# ISO_I2C_ISO1540DR.net
KiCad netlist of a schematic drawn in Altium Designer
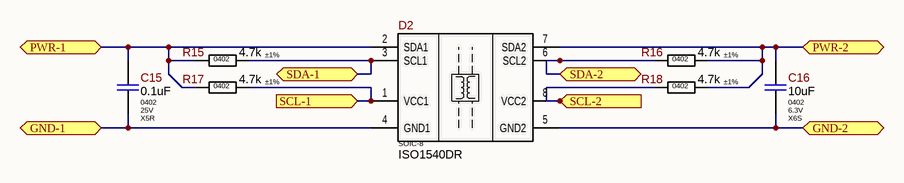
[diagram p0: ISO_I2C_ISO1540DR.SchDoc]

(export (version "E")
  (design (tool "Eeschema 10.0.6"))
  (components
    (comp (ref "C15")
      (value "0.1uF")
      (footprint "C_CERAMIC_0402_MED")
      (description "100nF 25V X5R ±10% 0402 Ceramic Capacitor RoHS")
      (fields
        (field (name "PACKAGE") "0402")
        (field (name "VOLTAGE") "25V")
        (field (name "DIELECTRIC TYPE") "X5R")
        (field (name "PART NUMBER") "CL05A104KA5NNNC")
        (field (name "MANUFACTURER") "Samsung Electro-Mechanics")
      )
      (libsource (lib "EL.XXX.T01") (part "Capacitor-NonPolar"))
    )
    (comp (ref "C16")
      (value "10uF")
      (footprint "C_CERAMIC_0402_MED")
      (description "10uF 6.3V X6S ±20% 0402 Ceramic Capacitor RoHS")
      (fields
        (field (name "PACKAGE") "0402")
        (field (name "VOLTAGE") "6.3V")
        (field (name "DIELECTRIC TYPE") "X6S")
        (field (name "PART NUMBER") "GRM155C80J106ME11D")
        (field (name "MANUFACTURER") "Murata Electronics")
      )
      (libsource (lib "EL.XXX.T01") (part "Capacitor-NonPolar"))
    )
    (comp (ref "D2")
      (value "ISO1540DR")
      (footprint "SOIC-8_W3.9MM")
      (description "I2C Digital Isolator 2500Vrms 2 Channel 1Mbps 25kV/us, SOIC-8")
      (fields
        (field (name "PACKAGE") "SOIC-8")
        (field (name "PART NUMBER") "ISO1540DR")
        (field (name "MANUFACTURER") "Texas Instruments")
      )
      (libsource (lib "EL.XXX.T01") (part "ISO1540DR"))
    )
    (comp (ref "R15")
      (value "4.7k")
      (footprint "R_ANY_CHIP_0402_MED")
      (description "4.7 kOhms ±1% 1/16W 0402 Thick Film Resistor")
      (fields
        (field (name "TOLERANCE") "±1%")
        (field (name "PACKAGE") "0402")
        (field (name "PART NUMBER") "RC0402FR-074K7L")
        (field (name "MANUFACTURER") "Yageo")
      )
      (libsource (lib "EL.XXX.T01") (part "Resistor"))
    )
    (comp (ref "R16")
      (value "4.7k")
      (footprint "R_ANY_CHIP_0402_MED")
      (description "4.7 kOhms ±1% 1/16W 0402 Thick Film Resistor")
      (fields
        (field (name "TOLERANCE") "±1%")
        (field (name "PACKAGE") "0402")
        (field (name "PART NUMBER") "RC0402FR-074K7L")
        (field (name "MANUFACTURER") "Yageo")
      )
      (libsource (lib "EL.XXX.T01") (part "Resistor"))
    )
    (comp (ref "R17")
      (value "4.7k")
      (footprint "R_ANY_CHIP_0402_MED")
      (description "4.7 kOhms ±1% 1/16W 0402 Thick Film Resistor")
      (fields
        (field (name "TOLERANCE") "±1%")
        (field (name "PACKAGE") "0402")
        (field (name "PART NUMBER") "RC0402FR-074K7L")
        (field (name "MANUFACTURER") "Yageo")
      )
      (libsource (lib "EL.XXX.T01") (part "Resistor"))
    )
    (comp (ref "R18")
      (value "4.7k")
      (footprint "R_ANY_CHIP_0402_MED")
      (description "4.7 kOhms ±1% 1/16W 0402 Thick Film Resistor")
      (fields
        (field (name "TOLERANCE") "±1%")
        (field (name "PACKAGE") "0402")
        (field (name "PART NUMBER") "RC0402FR-074K7L")
        (field (name "MANUFACTURER") "Yageo")
      )
      (libsource (lib "EL.XXX.T01") (part "Resistor"))
    )
  )
  (nets
    (net (code "1") (name "/GND-1") (class "Default")
      (node (ref "C15") (pin "2") (pinfunction "2_2") (pintype "passive"))
      (node (ref "D2") (pin "4") (pinfunction "GND1_4") (pintype "passive"))
    )
    (net (code "2") (name "/GND-2") (class "Default")
      (node (ref "C16") (pin "2") (pinfunction "2_2") (pintype "passive"))
      (node (ref "D2") (pin "5") (pinfunction "GND2_5") (pintype "passive"))
    )
    (net (code "3") (name "/PWR-1") (class "Default")
      (node (ref "C15") (pin "1") (pinfunction "1_1") (pintype "passive"))
      (node (ref "D2") (pin "2") (pinfunction "SDA1_2") (pintype "passive"))
      (node (ref "R15") (pin "1") (pintype "passive"))
      (node (ref "R17") (pin "1") (pintype "passive"))
    )
    (net (code "4") (name "/PWR-2") (class "Default")
      (node (ref "C16") (pin "1") (pinfunction "1_1") (pintype "passive"))
      (node (ref "D2") (pin "7") (pinfunction "SDA2_7") (pintype "passive"))
      (node (ref "R16") (pin "2") (pintype "passive"))
      (node (ref "R18") (pin "2") (pintype "passive"))
    )
    (net (code "5") (name "/SCL-1") (class "Default")
      (node (ref "D2") (pin "1") (pinfunction "VCC1_1") (pintype "passive"))
      (node (ref "R17") (pin "2") (pintype "passive"))
    )
    (net (code "6") (name "/SCL-2") (class "Default")
      (node (ref "D2") (pin "8") (pinfunction "VCC2_8") (pintype "passive"))
      (node (ref "R18") (pin "1") (pintype "passive"))
    )
    (net (code "7") (name "/SDA-1") (class "Default")
      (node (ref "D2") (pin "3") (pinfunction "SCL1_3") (pintype "passive"))
      (node (ref "R15") (pin "2") (pintype "passive"))
    )
    (net (code "8") (name "/SDA-2") (class "Default")
      (node (ref "D2") (pin "6") (pinfunction "SCL2_6") (pintype "passive"))
      (node (ref "R16") (pin "1") (pintype "passive"))
    )
  )
)
